# Schematic.net
KiCad netlist of a schematic drawn in Altium Designer
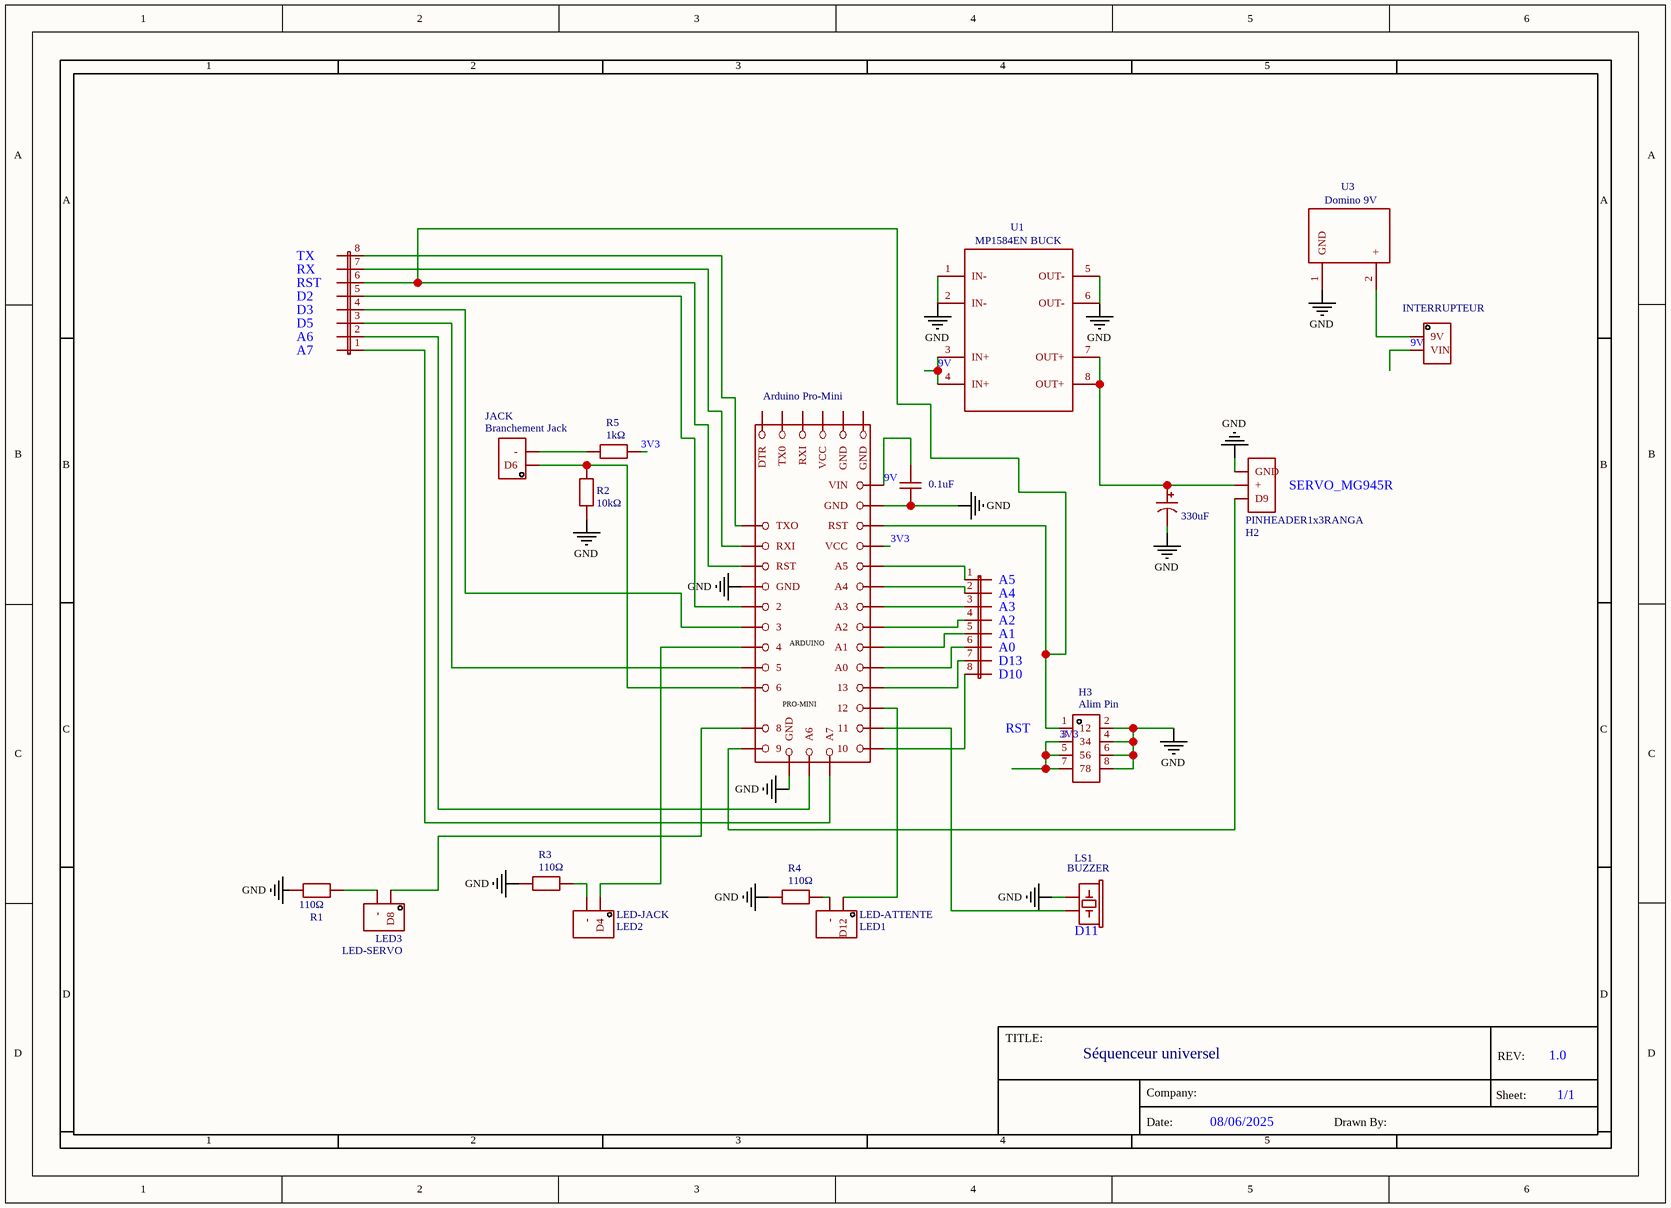
[diagram p0: Schematic.schdoc]

(export (version "E")
  (design (tool "Eeschema 10.0.6"))
  (components
    (comp (ref "C1")
      (value "330uF")
      (fields
        (field (name "MANUFACTURER") "CX(承兴)")
        (field (name "MANUFACTURER PART") "KM476M016D11RR0VH2FP0")
        (field (name "CONTRIBUTOR") "Reji S")
      )
      (libsource (lib "altium-import") (part "root_3_330uF_"))
    )
    (comp (ref "C2")
      (value "0.1uF")
      (fields
        (field (name "MANUFACTURER") "ValuePro")
        (field (name "MANUFACTURER PART") "Ceramic capacitor 150mil")
        (field (name "CONTRIBUTOR") "GireeshTS")
      )
      (libsource (lib "altium-import") (part "root_1_0.1uF_"))
    )
    (comp (ref "H2")
      (value "PINHEADER1x3RANGA")
      (fields (field (name "CONTRIBUTOR") "ranga404"))
      (libsource (lib "altium-import") (part "root_0_PINHEADER1x3RANGA_"))
    )
    (comp (ref "H3")
      (value "Alim Pin")
      (fields
        (field (name "MANUFACTURER") "INCP")
        (field (name "MANUFACTURER PART") "IPCP254M08PB28V")
        (field (name "CONTRIBUTOR") "lcsc")
      )
      (libsource (lib "altium-import") (part "root_0_Alim Pin_"))
    )
    (comp (ref "INTERRUPTEUR")
      (value "KCD1-101A")
      (fields (field (name "CONTRIBUTOR") "ahosahalli"))
      (libsource (lib "altium-import") (part "root_0_KCD1-101A_"))
    )
    (comp (ref "JACK")
      (value "Branchement Jack")
      (fields (field (name "CONTRIBUTOR") "ahosahalli"))
      (libsource (lib "altium-import") (part "root_2_Branchement Jack_"))
    )
    (comp (ref "JP1")
      (value "JUMPER-8-PINS")
      (fields (field (name "CONTRIBUTOR") "dina"))
      (libsource (lib "altium-import") (part "root_3_JUMPER-8-PINS_"))
    )
    (comp (ref "JP2")
      (value "JUMPER-8-PINS")
      (fields (field (name "CONTRIBUTOR") "dina"))
      (libsource (lib "altium-import") (part "root_1_JUMPER-8-PINS_"))
    )
    (comp (ref "LED-ATTENTE")
      (value "LED1")
      (fields (field (name "CONTRIBUTOR") "ahosahalli"))
      (libsource (lib "altium-import") (part "root_3_LED1_"))
    )
    (comp (ref "LED-JACK")
      (value "LED2")
      (fields (field (name "CONTRIBUTOR") "ahosahalli"))
      (libsource (lib "altium-import") (part "root_3_LED2_"))
    )
    (comp (ref "LED-SERVO")
      (value "LED3")
      (fields (field (name "CONTRIBUTOR") "ahosahalli"))
      (libsource (lib "altium-import") (part "root_1_LED3_"))
    )
    (comp (ref "LS1")
      (value "BUZZER")
      (fields (field (name "CONTRIBUTOR") "q2friki"))
      (libsource (lib "altium-import") (part "root_1_BUZZER_"))
    )
    (comp (ref "R1")
      (value "110Ω")
      (fields (field (name "CONTRIBUTOR") "matheopatino"))
      (libsource (lib "altium-import") (part "root_0_110Ω_"))
    )
    (comp (ref "R2")
      (value "10kΩ")
      (fields (field (name "CONTRIBUTOR") "matheopatino"))
      (libsource (lib "altium-import") (part "root_1_10kΩ_"))
    )
    (comp (ref "R3")
      (value "110Ω")
      (fields (field (name "CONTRIBUTOR") "matheopatino"))
      (libsource (lib "altium-import") (part "root_0_110Ω_"))
    )
    (comp (ref "R4")
      (value "110Ω")
      (fields (field (name "CONTRIBUTOR") "matheopatino"))
      (libsource (lib "altium-import") (part "root_0_110Ω_"))
    )
    (comp (ref "R5")
      (value "1kΩ")
      (fields (field (name "CONTRIBUTOR") "matheopatino"))
      (libsource (lib "altium-import") (part "root_2_1kΩ_"))
    )
    (comp (ref "U1")
      (value "MP1584EN BUCK")
      (fields (field (name "CONTRIBUTOR") "maxboudet_pcb"))
      (libsource (lib "altium-import") (part "root_0_MP1584EN BUCK_"))
    )
    (comp (ref "U2")
      (value "Arduino Pro-Mini")
      (fields (field (name "CONTRIBUTOR") "Dawid Karoński"))
      (libsource (lib "altium-import") (part "root_0_Arduino Pro-Mini_"))
    )
    (comp (ref "U3")
      (value "Domino 9V")
      (fields (field (name "CONTRIBUTOR") "maxboudet_pcb"))
      (libsource (lib "altium-import") (part "root_0_Domino 9V_"))
    )
  )
  (nets
    (net (code "1") (name "/3V3") (class "Default")
      (node (ref "H3") (pin "3") (pinfunction "3_3") (pintype "passive"))
      (node (ref "H3") (pin "5") (pinfunction "5_5") (pintype "passive"))
      (node (ref "H3") (pin "7") (pinfunction "7_7") (pintype "passive"))
      (node (ref "R5") (pin "1") (pinfunction "1_1") (pintype "passive"))
      (node (ref "U2") (pin "VCC") (pinfunction "VCC_VCC") (pintype "passive"))
    )
    (net (code "2") (name "/9V") (class "Default")
      (node (ref "C2") (pin "2") (pinfunction "2_2") (pintype "passive"))
      (node (ref "INTERRUPTEUR") (pin "2") (pinfunction "VIN_2") (pintype "passive"))
      (node (ref "U1") (pin "3") (pinfunction "IN+_3") (pintype "passive"))
      (node (ref "U1") (pin "4") (pinfunction "IN+_4") (pintype "passive"))
      (node (ref "U2") (pin "RAW") (pinfunction "VIN_RAW") (pintype "passive"))
    )
    (net (code "3") (name "GND") (class "Default")
      (node (ref "C1") (pin "2") (pinfunction "2_2") (pintype "passive"))
      (node (ref "C2") (pin "1") (pinfunction "1_1") (pintype "passive"))
      (node (ref "H2") (pin "3") (pinfunction "GND_3") (pintype "passive"))
      (node (ref "H3") (pin "2") (pinfunction "2_2") (pintype "passive"))
      (node (ref "H3") (pin "4") (pinfunction "4_4") (pintype "passive"))
      (node (ref "H3") (pin "6") (pinfunction "6_6") (pintype "passive"))
      (node (ref "H3") (pin "8") (pinfunction "8_8") (pintype "passive"))
      (node (ref "LS1") (pin "-") (pinfunction "2_-") (pintype "passive"))
      (node (ref "R1") (pin "1") (pinfunction "1_1") (pintype "passive"))
      (node (ref "R2") (pin "1") (pinfunction "1_1") (pintype "passive"))
      (node (ref "R3") (pin "1") (pinfunction "1_1") (pintype "passive"))
      (node (ref "R4") (pin "1") (pinfunction "1_1") (pintype "passive"))
      (node (ref "U1") (pin "1") (pinfunction "IN-_1") (pintype "passive"))
      (node (ref "U1") (pin "2") (pinfunction "IN-_2") (pintype "passive"))
      (node (ref "U1") (pin "5") (pinfunction "OUT-_5") (pintype "passive"))
      (node (ref "U1") (pin "6") (pinfunction "OUT-_6") (pintype "passive"))
      (node (ref "U2") (pin "GND") (pinfunction "GND_GND") (pintype "passive"))
      (node (ref "U2") (pin "GND@1") (pinfunction "GND_GND@1") (pintype "passive"))
      (node (ref "U2") (pin "GND@3") (pinfunction "GND_GND@3") (pintype "passive"))
      (node (ref "U3") (pin "1") (pinfunction "GND_1") (pintype "passive"))
    )
    (net (code "4") (name "Net-(H2-+)") (class "Default")
      (node (ref "C1") (pin "1") (pinfunction "1_1") (pintype "passive"))
      (node (ref "H2") (pin "2") (pinfunction "+_2") (pintype "passive"))
      (node (ref "U1") (pin "7") (pinfunction "OUT+_7") (pintype "passive"))
      (node (ref "U1") (pin "8") (pinfunction "OUT+_8") (pintype "passive"))
    )
    (net (code "5") (name "Net-(H2-D9)") (class "Default")
      (node (ref "H2") (pin "1") (pinfunction "D9_1") (pintype "passive"))
      (node (ref "U2") (pin "D9") (pinfunction "9_D9") (pintype "passive"))
    )
    (net (code "6") (name "Net-(H3-Pad1)") (class "Default")
      (node (ref "H3") (pin "1") (pinfunction "1_1") (pintype "passive"))
      (node (ref "JP2") (pin "6") (pinfunction "6_6") (pintype "passive"))
      (node (ref "U2") (pin "RST") (pinfunction "RST_RST") (pintype "passive"))
      (node (ref "U2") (pin "RST@1") (pinfunction "RST_RST@1") (pintype "passive"))
    )
    (net (code "7") (name "Net-(INTERRUPTEUR-9V)") (class "Default")
      (node (ref "INTERRUPTEUR") (pin "1") (pinfunction "9V_1") (pintype "passive"))
      (node (ref "U3") (pin "2") (pinfunction "+_2") (pintype "passive"))
    )
    (net (code "8") (name "Net-(JACK--)") (class "Default")
      (node (ref "JACK") (pin "2") (pinfunction "-_2") (pintype "passive"))
      (node (ref "R5") (pin "2") (pinfunction "2_2") (pintype "passive"))
    )
    (net (code "9") (name "Net-(JACK-D6)") (class "Default")
      (node (ref "JACK") (pin "1") (pinfunction "D6_1") (pintype "passive"))
      (node (ref "R2") (pin "2") (pinfunction "2_2") (pintype "passive"))
      (node (ref "U2") (pin "D6") (pinfunction "6_D6") (pintype "passive"))
    )
    (net (code "10") (name "Net-(JP1-Pad1)") (class "Default")
      (node (ref "JP1") (pin "1") (pinfunction "1_1") (pintype "passive"))
      (node (ref "U2") (pin "A5") (pinfunction "A5_A5") (pintype "passive"))
    )
    (net (code "11") (name "Net-(JP1-Pad2)") (class "Default")
      (node (ref "JP1") (pin "2") (pinfunction "2_2") (pintype "passive"))
      (node (ref "U2") (pin "A4") (pinfunction "A4_A4") (pintype "passive"))
    )
    (net (code "12") (name "Net-(JP1-Pad3)") (class "Default")
      (node (ref "JP1") (pin "3") (pinfunction "3_3") (pintype "passive"))
      (node (ref "U2") (pin "A3") (pinfunction "A3_A3") (pintype "passive"))
    )
    (net (code "13") (name "Net-(JP1-Pad4)") (class "Default")
      (node (ref "JP1") (pin "4") (pinfunction "4_4") (pintype "passive"))
      (node (ref "U2") (pin "A2") (pinfunction "A2_A2") (pintype "passive"))
    )
    (net (code "14") (name "Net-(JP1-Pad5)") (class "Default")
      (node (ref "JP1") (pin "5") (pinfunction "5_5") (pintype "passive"))
      (node (ref "U2") (pin "A1") (pinfunction "A1_A1") (pintype "passive"))
    )
    (net (code "15") (name "Net-(JP1-Pad6)") (class "Default")
      (node (ref "JP1") (pin "6") (pinfunction "6_6") (pintype "passive"))
      (node (ref "U2") (pin "A0") (pinfunction "A0_A0") (pintype "passive"))
    )
    (net (code "16") (name "Net-(JP2-Pad1)") (class "Default")
      (node (ref "JP2") (pin "1") (pinfunction "1_1") (pintype "passive"))
      (node (ref "U2") (pin "A7") (pinfunction "A7_A7") (pintype "passive"))
    )
    (net (code "17") (name "Net-(JP2-Pad2)") (class "Default")
      (node (ref "JP2") (pin "2") (pinfunction "2_2") (pintype "passive"))
      (node (ref "U2") (pin "A6") (pinfunction "A6_A6") (pintype "passive"))
    )
    (net (code "18") (name "Net-(JP2-Pad7)") (class "Default")
      (node (ref "JP2") (pin "7") (pinfunction "7_7") (pintype "passive"))
      (node (ref "U2") (pin "RX") (pinfunction "RXI_RX") (pintype "passive"))
    )
    (net (code "19") (name "Net-(LED-ATTENTE--)") (class "Default")
      (node (ref "LED-ATTENTE") (pin "2") (pinfunction "-_2") (pintype "passive"))
      (node (ref "R4") (pin "2") (pinfunction "2_2") (pintype "passive"))
    )
    (net (code "20") (name "Net-(LED-ATTENTE-D12)") (class "Default")
      (node (ref "LED-ATTENTE") (pin "1") (pinfunction "D12_1") (pintype "passive"))
      (node (ref "U2") (pin "D12") (pinfunction "12_D12") (pintype "passive"))
    )
    (net (code "21") (name "Net-(LED-JACK--)") (class "Default")
      (node (ref "LED-JACK") (pin "2") (pinfunction "-_2") (pintype "passive"))
      (node (ref "R3") (pin "2") (pinfunction "2_2") (pintype "passive"))
    )
    (net (code "22") (name "Net-(LED-JACK-D4)") (class "Default")
      (node (ref "LED-JACK") (pin "1") (pinfunction "D4_1") (pintype "passive"))
      (node (ref "U2") (pin "D4") (pinfunction "4_D4") (pintype "passive"))
    )
    (net (code "23") (name "Net-(LED-SERVO--)") (class "Default")
      (node (ref "LED-SERVO") (pin "2") (pinfunction "-_2") (pintype "passive"))
      (node (ref "R1") (pin "2") (pinfunction "2_2") (pintype "passive"))
    )
    (net (code "24") (name "Net-(LED-SERVO-D8)") (class "Default")
      (node (ref "LED-SERVO") (pin "1") (pinfunction "D8_1") (pintype "passive"))
      (node (ref "U2") (pin "D8") (pinfunction "8_D8") (pintype "passive"))
    )
    (net (code "25") (name "Net-(LS1-1)") (class "Default")
      (node (ref "LS1") (pin "+") (pinfunction "1_+") (pintype "passive"))
      (node (ref "U2") (pin "D11") (pinfunction "11_D11") (pintype "passive"))
    )
    (net (code "26") (name "Net-(U2-2)") (class "Default")
      (node (ref "JP2") (pin "5") (pinfunction "5_5") (pintype "passive"))
      (node (ref "U2") (pin "D2") (pinfunction "2_D2") (pintype "passive"))
    )
    (net (code "27") (name "Net-(U2-3)") (class "Default")
      (node (ref "JP2") (pin "4") (pinfunction "4_4") (pintype "passive"))
      (node (ref "U2") (pin "D3") (pinfunction "3_D3") (pintype "passive"))
    )
    (net (code "28") (name "Net-(U2-5)") (class "Default")
      (node (ref "JP2") (pin "3") (pinfunction "3_3") (pintype "passive"))
      (node (ref "U2") (pin "D5") (pinfunction "5_D5") (pintype "passive"))
    )
    (net (code "29") (name "Net-(U2-10)") (class "Default")
      (node (ref "JP1") (pin "8") (pinfunction "8_8") (pintype "passive"))
      (node (ref "U2") (pin "D10") (pinfunction "10_D10") (pintype "passive"))
    )
    (net (code "30") (name "Net-(U2-13)") (class "Default")
      (node (ref "JP1") (pin "7") (pinfunction "7_7") (pintype "passive"))
      (node (ref "U2") (pin "D13") (pinfunction "13_D13") (pintype "passive"))
    )
    (net (code "31") (name "Net-(U2-TXO)") (class "Default")
      (node (ref "JP2") (pin "8") (pinfunction "8_8") (pintype "passive"))
      (node (ref "U2") (pin "TX") (pinfunction "TXO_TX") (pintype "passive"))
    )
    (net (code "32") (name "unconnected-(U2-GND-PadBLK)") (class "Default")
      (node (ref "U2") (pin "BLK") (pinfunction "GND_BLK") (pintype "passive"))
    )
    (net (code "33") (name "unconnected-(U2-GND-PadGND@2)") (class "Default")
      (node (ref "U2") (pin "GND@2") (pinfunction "GND_GND@2") (pintype "passive"))
    )
    (net (code "34") (name "unconnected-(U2-PadDTR)") (class "Default")
      (node (ref "U2") (pin "DTR") (pinfunction "DTR_DTR") (pintype "passive"))
    )
    (net (code "35") (name "unconnected-(U2-RXI-PadRX@1)") (class "Default")
      (node (ref "U2") (pin "RX@1") (pinfunction "RXI_RX@1") (pintype "passive"))
    )
    (net (code "36") (name "unconnected-(U2-TX0-PadTX@1)") (class "Default")
      (node (ref "U2") (pin "TX@1") (pinfunction "TX0_TX@1") (pintype "passive"))
    )
    (net (code "37") (name "unconnected-(U2-VCC-PadVCC@1)") (class "Default")
      (node (ref "U2") (pin "VCC@1") (pinfunction "VCC_VCC@1") (pintype "passive"))
    )
  )
)
